# Alarm_Clock_Shematic.net
KiCad netlist of a schematic drawn in Altium Designer
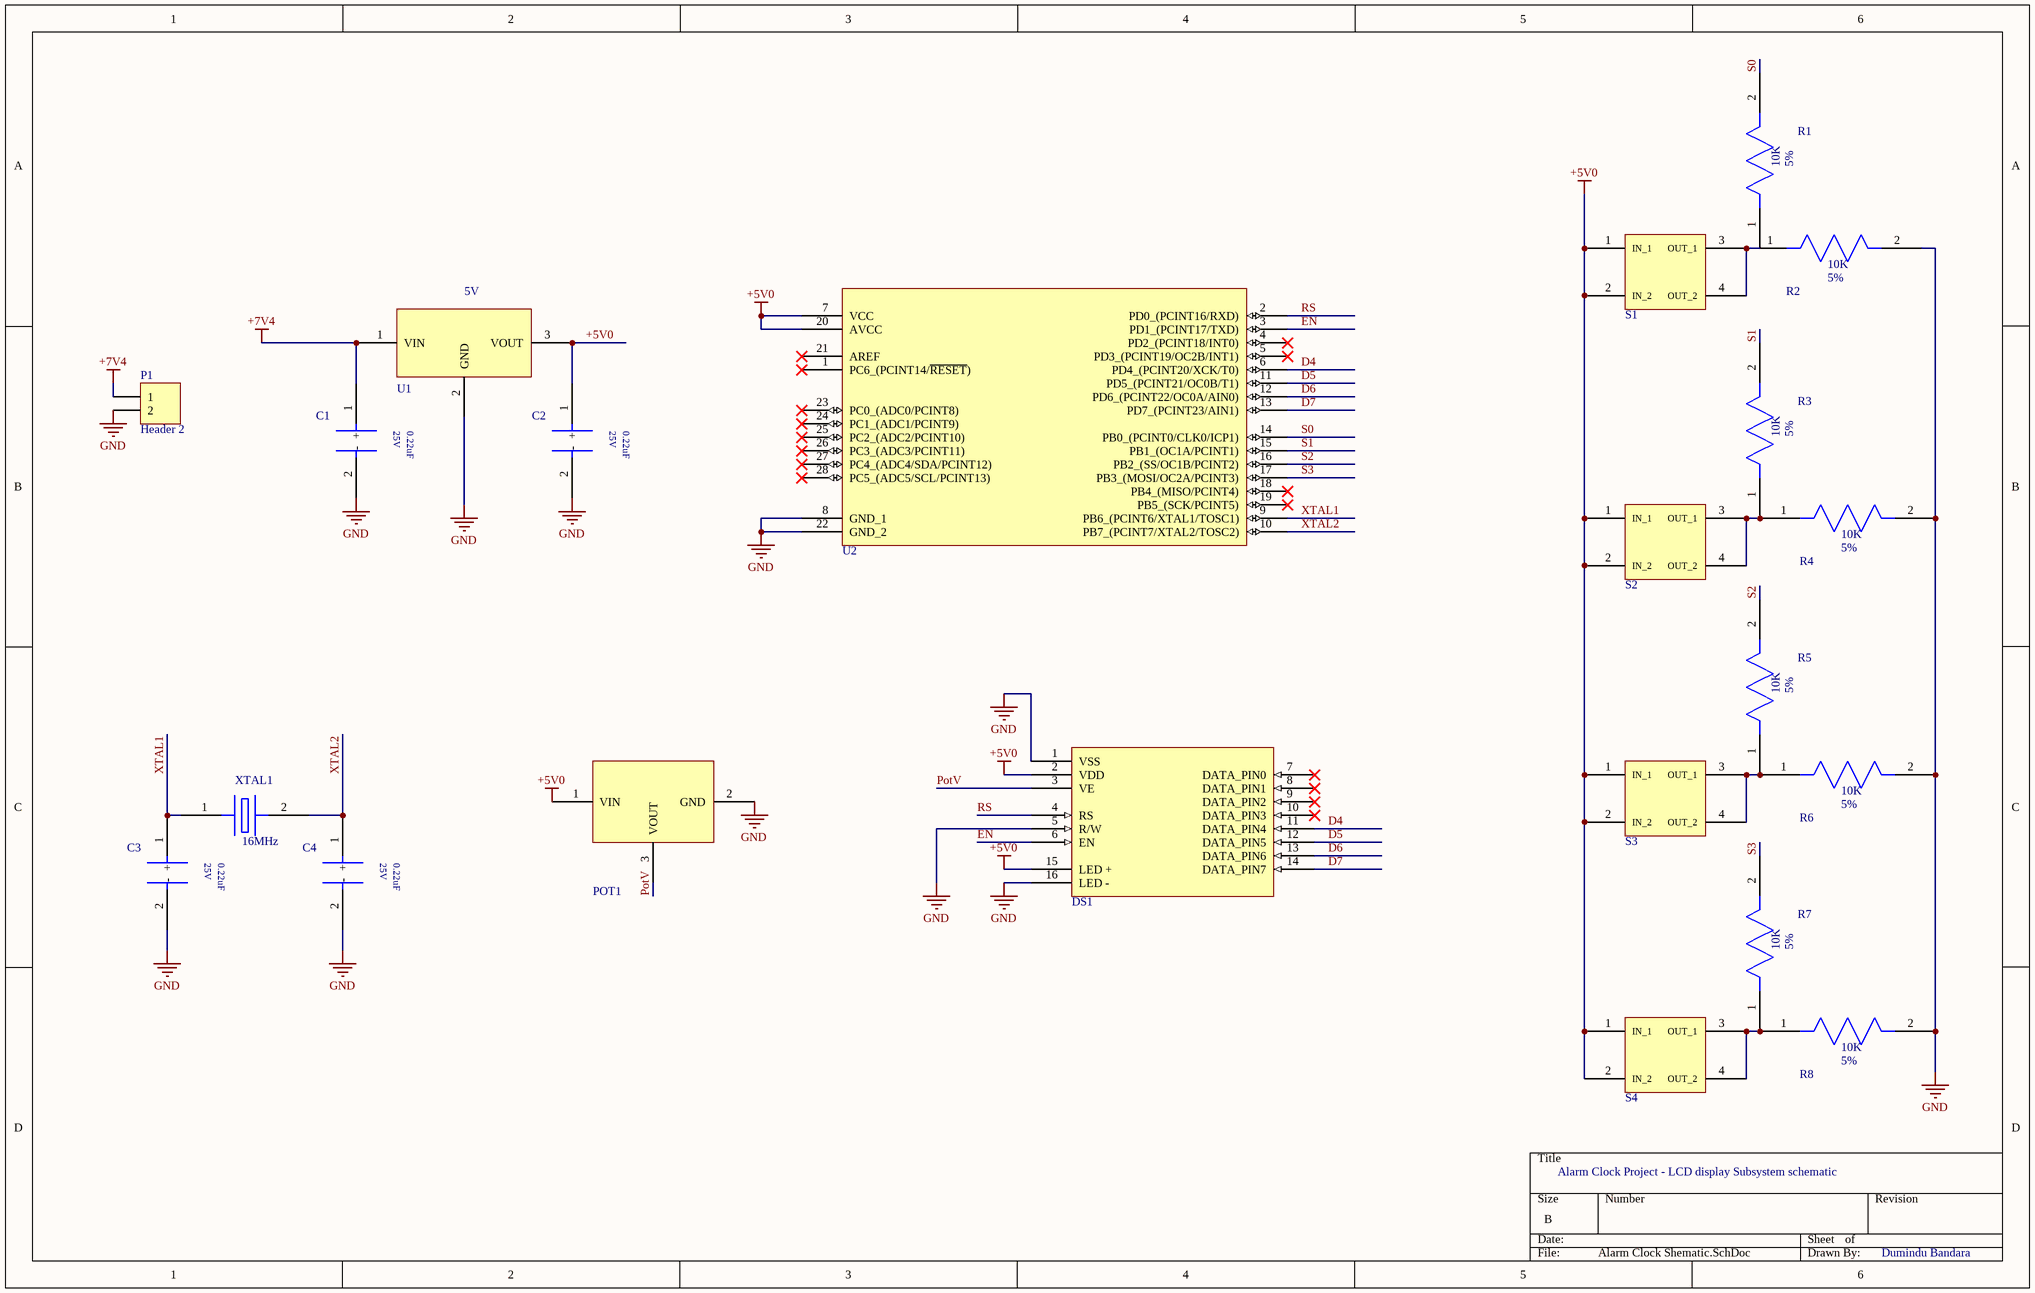
[diagram p0: Alarm Clock Shematic.SchDoc]

(export (version "E")
  (design (tool "Eeschema 10.0.6"))
  (components
    (comp (ref "C1")
      (value "Capacitor")
      (footprint "UMP1HR22MDD1TP")
      (description "Generic Capacitor")
      (fields (field (name "VOLTAGE") "25V"))
      (libsource (lib "Integrated_Library1") (part "Capacitor"))
    )
    (comp (ref "C2")
      (value "Capacitor")
      (footprint "UMP1HR22MDD1TP")
      (description "Generic Capacitor")
      (fields (field (name "VOLTAGE") "25V"))
      (libsource (lib "Integrated_Library1") (part "Capacitor"))
    )
    (comp (ref "C3")
      (value "Capacitor")
      (footprint "UMP1HR22MDD1TP")
      (description "Generic Capacitor")
      (fields (field (name "VOLTAGE") "25V"))
      (libsource (lib "Integrated_Library1") (part "Capacitor"))
    )
    (comp (ref "C4")
      (value "Capacitor")
      (footprint "UMP1HR22MDD1TP")
      (description "Generic Capacitor")
      (fields (field (name "VOLTAGE") "25V"))
      (libsource (lib "Integrated_Library1") (part "Capacitor"))
    )
    (comp (ref "DS1")
      (value "LM016L")
      (footprint "LCD DISPLAY")
      (description "16x2 LCD display with character size 5x8")
      (libsource (lib "Integrated_Library1") (part "LM016L"))
    )
    (comp (ref "P1")
      (value "Header 2")
      (footprint "HDR1X2")
      (description "Header, 2-Pin")
      (fields (field (name "PUBLISHER") "Altium Limited"))
      (libsource (lib "Miscellaneous Connectors") (part "Header 2"))
    )
    (comp (ref "POT1")
      (value "Variable Resistor")
      (footprint "10k Trimmer")
      (description "Variable resistor")
      (libsource (lib "Integrated_Library1") (part "Variable Resistor"))
    )
    (comp (ref "R1")
      (value "Resistor")
      (footprint "RESAD975W59L900D300")
      (description "Generic Resistor")
      (fields (field (name "TOLERANCE") "5%"))
      (libsource (lib "Integrated_Library1") (part "Resistor"))
    )
    (comp (ref "R2")
      (value "Resistor")
      (footprint "RESAD975W59L900D300")
      (description "Generic Resistor")
      (fields (field (name "TOLERANCE") "5%"))
      (libsource (lib "Integrated_Library1") (part "Resistor"))
    )
    (comp (ref "R3")
      (value "Resistor")
      (footprint "RESAD975W59L900D300")
      (description "Generic Resistor")
      (fields (field (name "TOLERANCE") "5%"))
      (libsource (lib "Integrated_Library1") (part "Resistor"))
    )
    (comp (ref "R4")
      (value "Resistor")
      (footprint "RESAD975W59L900D300")
      (description "Generic Resistor")
      (fields (field (name "TOLERANCE") "5%"))
      (libsource (lib "Integrated_Library1") (part "Resistor"))
    )
    (comp (ref "R5")
      (value "Resistor")
      (footprint "RESAD975W59L900D300")
      (description "Generic Resistor")
      (fields (field (name "TOLERANCE") "5%"))
      (libsource (lib "Integrated_Library1") (part "Resistor"))
    )
    (comp (ref "R6")
      (value "Resistor")
      (footprint "RESAD975W59L900D300")
      (description "Generic Resistor")
      (fields (field (name "TOLERANCE") "5%"))
      (libsource (lib "Integrated_Library1") (part "Resistor"))
    )
    (comp (ref "R7")
      (value "Resistor")
      (footprint "RESAD975W59L900D300")
      (description "Generic Resistor")
      (fields (field (name "TOLERANCE") "5%"))
      (libsource (lib "Integrated_Library1") (part "Resistor"))
    )
    (comp (ref "R8")
      (value "Resistor")
      (footprint "RESAD975W59L900D300")
      (description "Generic Resistor")
      (fields (field (name "TOLERANCE") "5%"))
      (libsource (lib "Integrated_Library1") (part "Resistor"))
    )
    (comp (ref "S1")
      (value "Push Button - SPST")
      (footprint "PUSH BUTTON")
      (description "Microswitch - SPST")
      (libsource (lib "Integrated_Library1") (part "Push Button - SPST"))
    )
    (comp (ref "S2")
      (value "Push Button - SPST")
      (footprint "PUSH BUTTON")
      (description "Microswitch - SPST")
      (libsource (lib "Integrated_Library1") (part "Push Button - SPST"))
    )
    (comp (ref "S3")
      (value "Push Button - SPST")
      (footprint "PUSH BUTTON")
      (description "Microswitch - SPST")
      (libsource (lib "Integrated_Library1") (part "Push Button - SPST"))
    )
    (comp (ref "S4")
      (value "Push Button - SPST")
      (footprint "PUSH BUTTON")
      (description "Microswitch - SPST")
      (libsource (lib "Integrated_Library1") (part "Push Button - SPST"))
    )
    (comp (ref "U1")
      (value "7805 Voltage Regulator")
      (footprint "TO255P1040X460X1968-3")
      (description "Linear 5V voltage regulator.")
      (libsource (lib "Integrated_Library1") (part "7805 Voltage Regulator"))
    )
    (comp (ref "U2")
      (value "Atmega 328P U")
      (footprint "DIP793W45P254L3479H457Q28")
      (description "AVR series Microcontroller IC 8-Bit 20MHz 32KB (16K x 16) FLASH 28-PDIP")
      (libsource (lib "Integrated_Library1") (part "Atmega 328P U"))
    )
    (comp (ref "XTAL1")
      (value "Crystal")
      (footprint "ECS-160-20-4VX")
      (description "Crystal Oscillator")
      (libsource (lib "Integrated_Library1") (part "Crystal"))
    )
  )
  (nets
    (net (code "1") (name "+5V0") (class "Default")
      (node (ref "C2") (pin "1") (pinfunction "+_1") (pintype "passive"))
      (node (ref "DS1") (pin "15") (pinfunction "LED_+_15") (pintype "passive"))
      (node (ref "DS1") (pin "2") (pinfunction "VDD_2") (pintype "passive"))
      (node (ref "POT1") (pin "1") (pinfunction "VIN_1") (pintype "passive"))
      (node (ref "S1") (pin "1") (pinfunction "IN_1_1") (pintype "passive"))
      (node (ref "S1") (pin "2") (pinfunction "IN_2_2") (pintype "passive"))
      (node (ref "S2") (pin "1") (pinfunction "IN_1_1") (pintype "passive"))
      (node (ref "S2") (pin "2") (pinfunction "IN_2_2") (pintype "passive"))
      (node (ref "S3") (pin "1") (pinfunction "IN_1_1") (pintype "passive"))
      (node (ref "S3") (pin "2") (pinfunction "IN_2_2") (pintype "passive"))
      (node (ref "S4") (pin "1") (pinfunction "IN_1_1") (pintype "passive"))
      (node (ref "S4") (pin "2") (pinfunction "IN_2_2") (pintype "passive"))
      (node (ref "U1") (pin "3") (pinfunction "VOUT_3") (pintype "passive"))
      (node (ref "U2") (pin "20") (pinfunction "AVCC_20") (pintype "passive"))
      (node (ref "U2") (pin "7") (pinfunction "VCC_7") (pintype "passive"))
    )
    (net (code "2") (name "+7V4") (class "Default")
      (node (ref "C1") (pin "1") (pinfunction "+_1") (pintype "passive"))
      (node (ref "P1") (pin "1") (pinfunction "1_1") (pintype "passive"))
      (node (ref "U1") (pin "1") (pinfunction "VIN_1") (pintype "passive"))
    )
    (net (code "3") (name "/D4") (class "Default")
      (node (ref "DS1") (pin "11") (pinfunction "DATA_PIN4_11") (pintype "input"))
      (node (ref "U2") (pin "6") (pinfunction "PD4_(PCINT20/XCK/T0)_6") (pintype "bidirectional"))
    )
    (net (code "4") (name "/D5") (class "Default")
      (node (ref "DS1") (pin "12") (pinfunction "DATA_PIN5_12") (pintype "input"))
      (node (ref "U2") (pin "11") (pinfunction "PD5_(PCINT21/OC0B/T1)_11") (pintype "bidirectional"))
    )
    (net (code "5") (name "/D6") (class "Default")
      (node (ref "DS1") (pin "13") (pinfunction "DATA_PIN6_13") (pintype "input"))
      (node (ref "U2") (pin "12") (pinfunction "PD6_(PCINT22/OC0A/AIN0)_12") (pintype "bidirectional"))
    )
    (net (code "6") (name "/D7") (class "Default")
      (node (ref "DS1") (pin "14") (pinfunction "DATA_PIN7_14") (pintype "input"))
      (node (ref "U2") (pin "13") (pinfunction "PD7_(PCINT23/AIN1)_13") (pintype "bidirectional"))
    )
    (net (code "7") (name "/EN") (class "Default")
      (node (ref "DS1") (pin "6") (pinfunction "EN_6") (pintype "input"))
      (node (ref "U2") (pin "3") (pinfunction "PD1_(PCINT17/TXD)_3") (pintype "bidirectional"))
    )
    (net (code "8") (name "/PotV") (class "Default")
      (node (ref "DS1") (pin "3") (pinfunction "VE_3") (pintype "passive"))
      (node (ref "POT1") (pin "3") (pinfunction "VOUT_3") (pintype "passive"))
    )
    (net (code "9") (name "/RS") (class "Default")
      (node (ref "DS1") (pin "4") (pinfunction "RS_4") (pintype "input"))
      (node (ref "U2") (pin "2") (pinfunction "PD0_(PCINT16/RXD)_2") (pintype "bidirectional"))
    )
    (net (code "10") (name "/S0") (class "Default")
      (node (ref "R1") (pin "2") (pintype "passive"))
      (node (ref "U2") (pin "14") (pinfunction "PB0_(PCINT0/CLK0/ICP1)_14") (pintype "bidirectional"))
    )
    (net (code "11") (name "/S1") (class "Default")
      (node (ref "R3") (pin "2") (pintype "passive"))
      (node (ref "U2") (pin "15") (pinfunction "PB1_(OC1A/PCINT1)_15") (pintype "bidirectional"))
    )
    (net (code "12") (name "/S2") (class "Default")
      (node (ref "R5") (pin "2") (pintype "passive"))
      (node (ref "U2") (pin "16") (pinfunction "PB2_(SS/OC1B/PCINT2)_16") (pintype "bidirectional"))
    )
    (net (code "13") (name "/S3") (class "Default")
      (node (ref "R7") (pin "2") (pintype "passive"))
      (node (ref "U2") (pin "17") (pinfunction "PB3_(MOSI/OC2A/PCINT3)_17") (pintype "bidirectional"))
    )
    (net (code "14") (name "/XTAL1") (class "Default")
      (node (ref "C3") (pin "1") (pinfunction "+_1") (pintype "passive"))
      (node (ref "U2") (pin "9") (pinfunction "PB6_(PCINT6/XTAL1/TOSC1)_9") (pintype "bidirectional"))
      (node (ref "XTAL1") (pin "1") (pintype "passive"))
    )
    (net (code "15") (name "/XTAL2") (class "Default")
      (node (ref "C4") (pin "1") (pinfunction "+_1") (pintype "passive"))
      (node (ref "U2") (pin "10") (pinfunction "PB7_(PCINT7/XTAL2/TOSC2)_10") (pintype "bidirectional"))
      (node (ref "XTAL1") (pin "2") (pintype "passive"))
    )
    (net (code "16") (name "GND") (class "Default")
      (node (ref "C1") (pin "2") (pinfunction "-_2") (pintype "passive"))
      (node (ref "C2") (pin "2") (pinfunction "-_2") (pintype "passive"))
      (node (ref "C3") (pin "2") (pinfunction "-_2") (pintype "passive"))
      (node (ref "C4") (pin "2") (pinfunction "-_2") (pintype "passive"))
      (node (ref "DS1") (pin "1") (pinfunction "VSS_1") (pintype "passive"))
      (node (ref "DS1") (pin "16") (pinfunction "LED_-_16") (pintype "passive"))
      (node (ref "DS1") (pin "5") (pinfunction "R/W_5") (pintype "input"))
      (node (ref "P1") (pin "2") (pinfunction "2_2") (pintype "passive"))
      (node (ref "POT1") (pin "2") (pinfunction "GND_2") (pintype "passive"))
      (node (ref "R2") (pin "2") (pintype "passive"))
      (node (ref "R4") (pin "2") (pintype "passive"))
      (node (ref "R6") (pin "2") (pintype "passive"))
      (node (ref "R8") (pin "2") (pintype "passive"))
      (node (ref "U1") (pin "2") (pinfunction "GND_2") (pintype "passive"))
      (node (ref "U2") (pin "22") (pinfunction "GND_2_22") (pintype "passive"))
      (node (ref "U2") (pin "8") (pinfunction "GND_1_8") (pintype "passive"))
    )
    (net (code "17") (name "Net-(S1-OUT_1)") (class "Default")
      (node (ref "R1") (pin "1") (pintype "passive"))
      (node (ref "R2") (pin "1") (pintype "passive"))
      (node (ref "S1") (pin "3") (pinfunction "OUT_1_3") (pintype "passive"))
      (node (ref "S1") (pin "4") (pinfunction "OUT_2_4") (pintype "passive"))
    )
    (net (code "18") (name "Net-(S2-OUT_1)") (class "Default")
      (node (ref "R3") (pin "1") (pintype "passive"))
      (node (ref "R4") (pin "1") (pintype "passive"))
      (node (ref "S2") (pin "3") (pinfunction "OUT_1_3") (pintype "passive"))
      (node (ref "S2") (pin "4") (pinfunction "OUT_2_4") (pintype "passive"))
    )
    (net (code "19") (name "Net-(S3-OUT_1)") (class "Default")
      (node (ref "R5") (pin "1") (pintype "passive"))
      (node (ref "R6") (pin "1") (pintype "passive"))
      (node (ref "S3") (pin "3") (pinfunction "OUT_1_3") (pintype "passive"))
      (node (ref "S3") (pin "4") (pinfunction "OUT_2_4") (pintype "passive"))
    )
    (net (code "20") (name "Net-(S4-OUT_1)") (class "Default")
      (node (ref "R7") (pin "1") (pintype "passive"))
      (node (ref "R8") (pin "1") (pintype "passive"))
      (node (ref "S4") (pin "3") (pinfunction "OUT_1_3") (pintype "passive"))
      (node (ref "S4") (pin "4") (pinfunction "OUT_2_4") (pintype "passive"))
    )
    (net (code "21") (name "unconnected-(DS1-DATA_PIN0-Pad7)") (class "Default")
      (node (ref "DS1") (pin "7") (pinfunction "DATA_PIN0_7") (pintype "input+no_connect"))
    )
    (net (code "22") (name "unconnected-(DS1-DATA_PIN1-Pad8)") (class "Default")
      (node (ref "DS1") (pin "8") (pinfunction "DATA_PIN1_8") (pintype "input+no_connect"))
    )
    (net (code "23") (name "unconnected-(DS1-DATA_PIN2-Pad9)") (class "Default")
      (node (ref "DS1") (pin "9") (pinfunction "DATA_PIN2_9") (pintype "input+no_connect"))
    )
    (net (code "24") (name "unconnected-(DS1-DATA_PIN3-Pad10)") (class "Default")
      (node (ref "DS1") (pin "10") (pinfunction "DATA_PIN3_10") (pintype "input+no_connect"))
    )
    (net (code "25") (name "unconnected-(U2-AREF-Pad21)") (class "Default")
      (node (ref "U2") (pin "21") (pinfunction "AREF_21") (pintype "passive+no_connect"))
    )
    (net (code "26") (name "unconnected-(U2-PB4_(MISO{slash}PCINT4)-Pad18)") (class "Default")
      (node (ref "U2") (pin "18") (pinfunction "PB4_(MISO/PCINT4)_18") (pintype "bidirectional+no_connect"))
    )
    (net (code "27") (name "unconnected-(U2-PB5_(SCK{slash}PCINT5)-Pad19)") (class "Default")
      (node (ref "U2") (pin "19") (pinfunction "PB5_(SCK/PCINT5)_19") (pintype "bidirectional+no_connect"))
    )
    (net (code "28") (name "unconnected-(U2-PC0_(ADC0{slash}PCINT8)-Pad23)") (class "Default")
      (node (ref "U2") (pin "23") (pinfunction "PC0_(ADC0/PCINT8)_23") (pintype "bidirectional+no_connect"))
    )
    (net (code "29") (name "unconnected-(U2-PC1_(ADC1{slash}PCINT9)-Pad24)") (class "Default")
      (node (ref "U2") (pin "24") (pinfunction "PC1_(ADC1/PCINT9)_24") (pintype "bidirectional+no_connect"))
    )
    (net (code "30") (name "unconnected-(U2-PC2_(ADC2{slash}PCINT10)-Pad25)") (class "Default")
      (node (ref "U2") (pin "25") (pinfunction "PC2_(ADC2/PCINT10)_25") (pintype "bidirectional+no_connect"))
    )
    (net (code "31") (name "unconnected-(U2-PC3_(ADC3{slash}PCINT11)-Pad26)") (class "Default")
      (node (ref "U2") (pin "26") (pinfunction "PC3_(ADC3/PCINT11)_26") (pintype "bidirectional+no_connect"))
    )
    (net (code "32") (name "unconnected-(U2-PC4_(ADC4{slash}SDA{slash}PCINT12)-Pad27)") (class "Default")
      (node (ref "U2") (pin "27") (pinfunction "PC4_(ADC4/SDA/PCINT12)_27") (pintype "bidirectional+no_connect"))
    )
    (net (code "33") (name "unconnected-(U2-PC5_(ADC5{slash}SCL{slash}PCINT13)-Pad28)") (class "Default")
      (node (ref "U2") (pin "28") (pinfunction "PC5_(ADC5/SCL/PCINT13)_28") (pintype "bidirectional+no_connect"))
    )
    (net (code "34") (name "unconnected-(U2-PC6_(PCINT14{slash}~{RESET})-Pad1)") (class "Default")
      (node (ref "U2") (pin "1") (pinfunction "PC6_(PCINT14/~{RESET})_1") (pintype "passive+no_connect"))
    )
    (net (code "35") (name "unconnected-(U2-PD2_(PCINT18{slash}INT0)-Pad4)") (class "Default")
      (node (ref "U2") (pin "4") (pinfunction "PD2_(PCINT18/INT0)_4") (pintype "bidirectional+no_connect"))
    )
    (net (code "36") (name "unconnected-(U2-PD3_(PCINT19{slash}OC2B{slash}INT1)-Pad5)") (class "Default")
      (node (ref "U2") (pin "5") (pinfunction "PD3_(PCINT19/OC2B/INT1)_5") (pintype "bidirectional+no_connect"))
    )
  )
)
